# controller.net
KiCad netlist of a schematic drawn in EAGLE
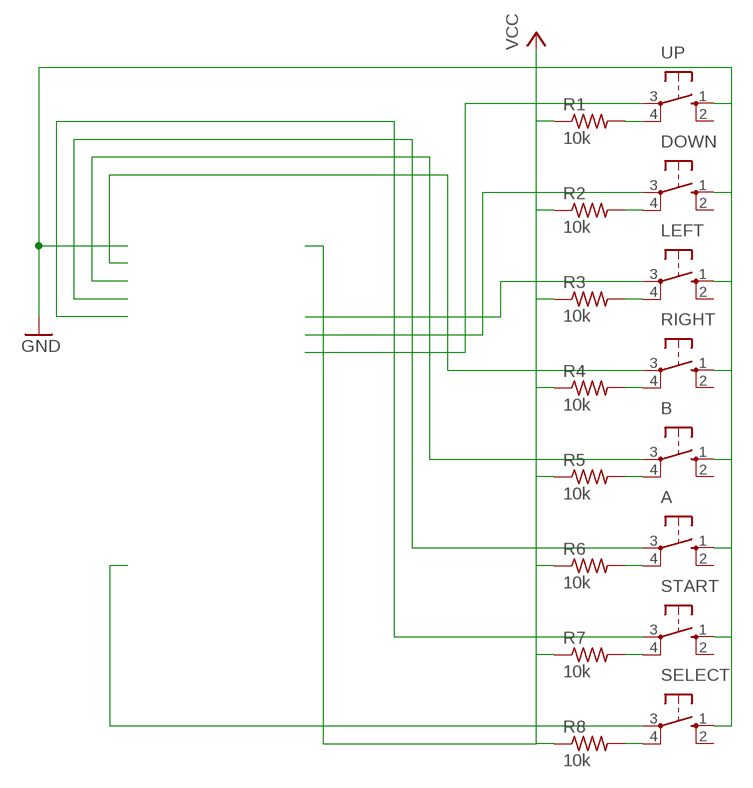
[diagram p0: schematic, sheet 1]

(export (version "E")
  (design (tool "Eeschema 10.0.6"))
  (components
    (comp (ref "A")
      (value "10-XX")
      (footprint "eagle-import:B3F-10XX")
      (fields (field (name "MPN") "B3F-1000"))
      (libsource (lib "eagle-import") (part "10-XX"))
    )
    (comp (ref "B")
      (value "10-XX")
      (footprint "eagle-import:B3F-10XX")
      (fields (field (name "MPN") "B3F-1000"))
      (libsource (lib "eagle-import") (part "10-XX"))
    )
    (comp (ref "DOWN")
      (value "10-XX")
      (footprint "eagle-import:B3F-10XX")
      (fields (field (name "MPN") "B3F-1000"))
      (libsource (lib "eagle-import") (part "10-XX"))
    )
    (comp (ref "LEFT")
      (value "10-XX")
      (footprint "eagle-import:B3F-10XX")
      (fields (field (name "MPN") "B3F-1000"))
      (libsource (lib "eagle-import") (part "10-XX"))
    )
    (comp (ref "R1")
      (value "10k")
      (footprint "eagle-import:0204_7")
      (libsource (lib "eagle-import") (part "R-US_0204/7"))
    )
    (comp (ref "R2")
      (value "10k")
      (footprint "eagle-import:0204_7")
      (libsource (lib "eagle-import") (part "R-US_0204/7"))
    )
    (comp (ref "R3")
      (value "10k")
      (footprint "eagle-import:0204_7")
      (libsource (lib "eagle-import") (part "R-US_0204/7"))
    )
    (comp (ref "R4")
      (value "10k")
      (footprint "eagle-import:0204_7")
      (libsource (lib "eagle-import") (part "R-US_0204/7"))
    )
    (comp (ref "R5")
      (value "10k")
      (footprint "eagle-import:0204_7")
      (libsource (lib "eagle-import") (part "R-US_0204/7"))
    )
    (comp (ref "R6")
      (value "10k")
      (footprint "eagle-import:0204_7")
      (libsource (lib "eagle-import") (part "R-US_0204/7"))
    )
    (comp (ref "R7")
      (value "10k")
      (footprint "eagle-import:0204_7")
      (libsource (lib "eagle-import") (part "R-US_0204/7"))
    )
    (comp (ref "R8")
      (value "10k")
      (footprint "eagle-import:0204_7")
      (libsource (lib "eagle-import") (part "R-US_0204/7"))
    )
    (comp (ref "RIGHT")
      (value "10-XX")
      (footprint "eagle-import:B3F-10XX")
      (fields (field (name "MPN") "B3F-1000"))
      (libsource (lib "eagle-import") (part "10-XX"))
    )
    (comp (ref "SELECT")
      (value "10-XX")
      (footprint "eagle-import:B3F-10XX")
      (fields (field (name "MPN") "B3F-1000"))
      (libsource (lib "eagle-import") (part "10-XX"))
    )
    (comp (ref "START")
      (value "10-XX")
      (footprint "eagle-import:B3F-10XX")
      (fields (field (name "MPN") "B3F-1000"))
      (libsource (lib "eagle-import") (part "10-XX"))
    )
    (comp (ref "UP")
      (value "10-XX")
      (footprint "eagle-import:B3F-10XX")
      (fields (field (name "MPN") "B3F-1000"))
      (libsource (lib "eagle-import") (part "10-XX"))
    )
  )
  (nets
    (net (code "1") (name "GND") (class "Default")
      (node (ref "A") (pin "1") (pinfunction "S_1") (pintype "passive"))
      (node (ref "B") (pin "1") (pinfunction "S_1") (pintype "passive"))
      (node (ref "DOWN") (pin "1") (pinfunction "S_1") (pintype "passive"))
      (node (ref "LEFT") (pin "1") (pinfunction "S_1") (pintype "passive"))
      (node (ref "RIGHT") (pin "1") (pinfunction "S_1") (pintype "passive"))
      (node (ref "SELECT") (pin "1") (pinfunction "S_1") (pintype "passive"))
      (node (ref "START") (pin "1") (pinfunction "S_1") (pintype "passive"))
      (node (ref "UP") (pin "1") (pinfunction "S_1") (pintype "passive"))
    )
    (net (code "2") (name "Net-(A-P1)") (class "Default")
      (node (ref "A") (pin "4") (pinfunction "P1_4") (pintype "passive"))
      (node (ref "R6") (pin "2") (pinfunction "2_2") (pintype "passive"))
    )
    (net (code "3") (name "Net-(B-P1)") (class "Default")
      (node (ref "B") (pin "4") (pinfunction "P1_4") (pintype "passive"))
      (node (ref "R5") (pin "2") (pinfunction "2_2") (pintype "passive"))
    )
    (net (code "4") (name "Net-(DOWN-P1)") (class "Default")
      (node (ref "DOWN") (pin "4") (pinfunction "P1_4") (pintype "passive"))
      (node (ref "R2") (pin "2") (pinfunction "2_2") (pintype "passive"))
    )
    (net (code "5") (name "Net-(LEFT-P1)") (class "Default")
      (node (ref "LEFT") (pin "4") (pinfunction "P1_4") (pintype "passive"))
      (node (ref "R3") (pin "2") (pinfunction "2_2") (pintype "passive"))
    )
    (net (code "6") (name "Net-(RIGHT-P1)") (class "Default")
      (node (ref "R4") (pin "2") (pinfunction "2_2") (pintype "passive"))
      (node (ref "RIGHT") (pin "4") (pinfunction "P1_4") (pintype "passive"))
    )
    (net (code "7") (name "Net-(SELECT-P1)") (class "Default")
      (node (ref "R8") (pin "2") (pinfunction "2_2") (pintype "passive"))
      (node (ref "SELECT") (pin "4") (pinfunction "P1_4") (pintype "passive"))
    )
    (net (code "8") (name "Net-(START-P1)") (class "Default")
      (node (ref "R7") (pin "2") (pinfunction "2_2") (pintype "passive"))
      (node (ref "START") (pin "4") (pinfunction "P1_4") (pintype "passive"))
    )
    (net (code "9") (name "Net-(UP-P1)") (class "Default")
      (node (ref "R1") (pin "2") (pinfunction "2_2") (pintype "passive"))
      (node (ref "UP") (pin "4") (pinfunction "P1_4") (pintype "passive"))
    )
    (net (code "10") (name "VCC") (class "Default")
      (node (ref "R1") (pin "1") (pinfunction "1_1") (pintype "passive"))
      (node (ref "R2") (pin "1") (pinfunction "1_1") (pintype "passive"))
      (node (ref "R3") (pin "1") (pinfunction "1_1") (pintype "passive"))
      (node (ref "R4") (pin "1") (pinfunction "1_1") (pintype "passive"))
      (node (ref "R5") (pin "1") (pinfunction "1_1") (pintype "passive"))
      (node (ref "R6") (pin "1") (pinfunction "1_1") (pintype "passive"))
      (node (ref "R7") (pin "1") (pinfunction "1_1") (pintype "passive"))
      (node (ref "R8") (pin "1") (pinfunction "1_1") (pintype "passive"))
    )
    (net (code "11") (name "unconnected-(A-P-Pad3)") (class "Default")
      (node (ref "A") (pin "3") (pinfunction "P_3") (pintype "passive"))
    )
    (net (code "12") (name "unconnected-(A-S1-Pad2)") (class "Default")
      (node (ref "A") (pin "2") (pinfunction "S1_2") (pintype "passive"))
    )
    (net (code "13") (name "unconnected-(B-P-Pad3)") (class "Default")
      (node (ref "B") (pin "3") (pinfunction "P_3") (pintype "passive"))
    )
    (net (code "14") (name "unconnected-(B-S1-Pad2)") (class "Default")
      (node (ref "B") (pin "2") (pinfunction "S1_2") (pintype "passive"))
    )
    (net (code "15") (name "unconnected-(DOWN-P-Pad3)") (class "Default")
      (node (ref "DOWN") (pin "3") (pinfunction "P_3") (pintype "passive"))
    )
    (net (code "16") (name "unconnected-(DOWN-S1-Pad2)") (class "Default")
      (node (ref "DOWN") (pin "2") (pinfunction "S1_2") (pintype "passive"))
    )
    (net (code "17") (name "unconnected-(LEFT-P-Pad3)") (class "Default")
      (node (ref "LEFT") (pin "3") (pinfunction "P_3") (pintype "passive"))
    )
    (net (code "18") (name "unconnected-(LEFT-S1-Pad2)") (class "Default")
      (node (ref "LEFT") (pin "2") (pinfunction "S1_2") (pintype "passive"))
    )
    (net (code "19") (name "unconnected-(RIGHT-P-Pad3)") (class "Default")
      (node (ref "RIGHT") (pin "3") (pinfunction "P_3") (pintype "passive"))
    )
    (net (code "20") (name "unconnected-(RIGHT-S1-Pad2)") (class "Default")
      (node (ref "RIGHT") (pin "2") (pinfunction "S1_2") (pintype "passive"))
    )
    (net (code "21") (name "unconnected-(SELECT-P-Pad3)") (class "Default")
      (node (ref "SELECT") (pin "3") (pinfunction "P_3") (pintype "passive"))
    )
    (net (code "22") (name "unconnected-(SELECT-S1-Pad2)") (class "Default")
      (node (ref "SELECT") (pin "2") (pinfunction "S1_2") (pintype "passive"))
    )
    (net (code "23") (name "unconnected-(START-P-Pad3)") (class "Default")
      (node (ref "START") (pin "3") (pinfunction "P_3") (pintype "passive"))
    )
    (net (code "24") (name "unconnected-(START-S1-Pad2)") (class "Default")
      (node (ref "START") (pin "2") (pinfunction "S1_2") (pintype "passive"))
    )
    (net (code "25") (name "unconnected-(UP-P-Pad3)") (class "Default")
      (node (ref "UP") (pin "3") (pinfunction "P_3") (pintype "passive"))
    )
    (net (code "26") (name "unconnected-(UP-S1-Pad2)") (class "Default")
      (node (ref "UP") (pin "2") (pinfunction "S1_2") (pintype "passive"))
    )
  )
)
